# femtoBeacon-BT5_r1_0_0.net
KiCad netlist of a schematic drawn in EAGLE
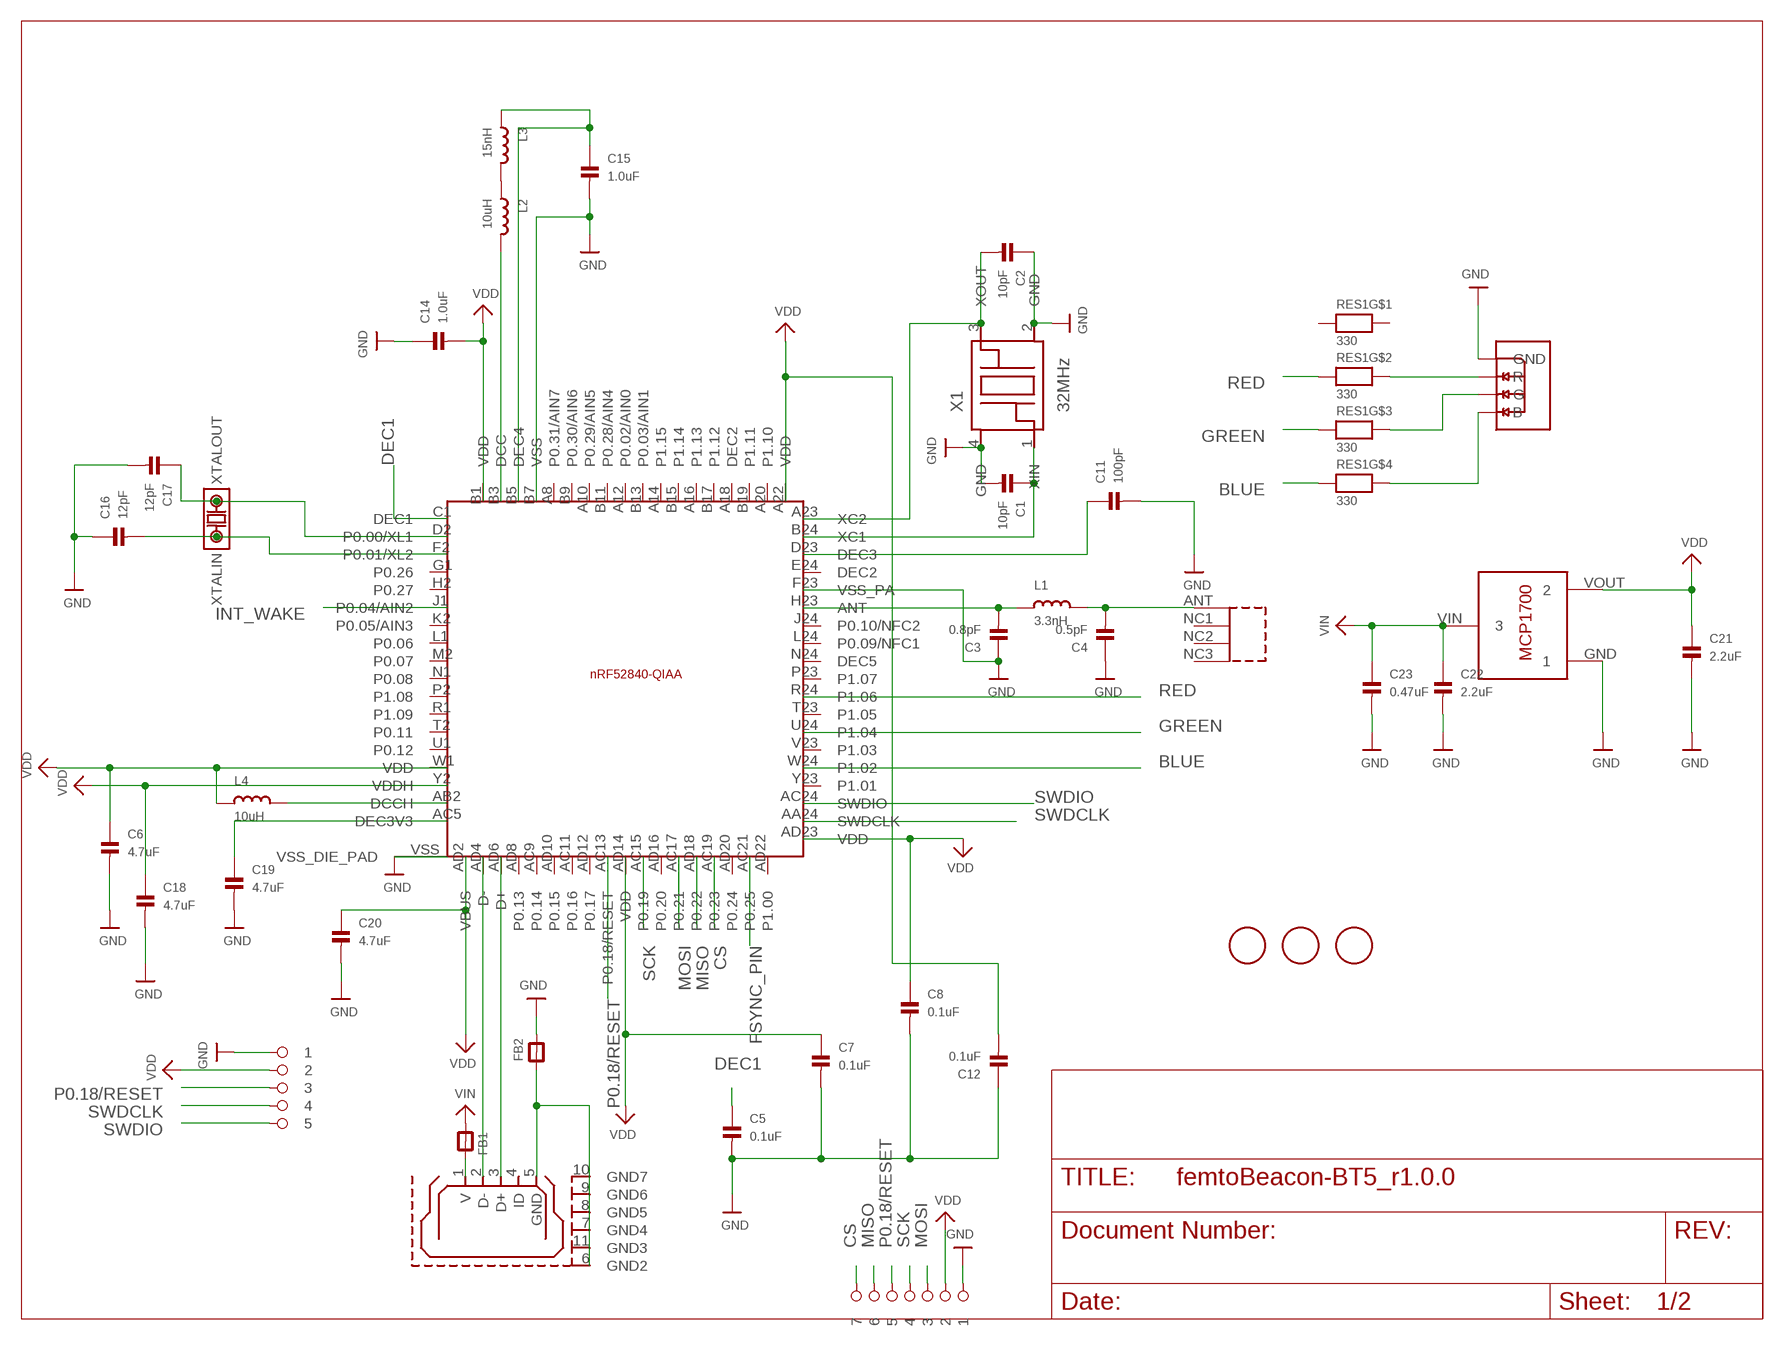
[diagram p0: schematic, sheet 1]
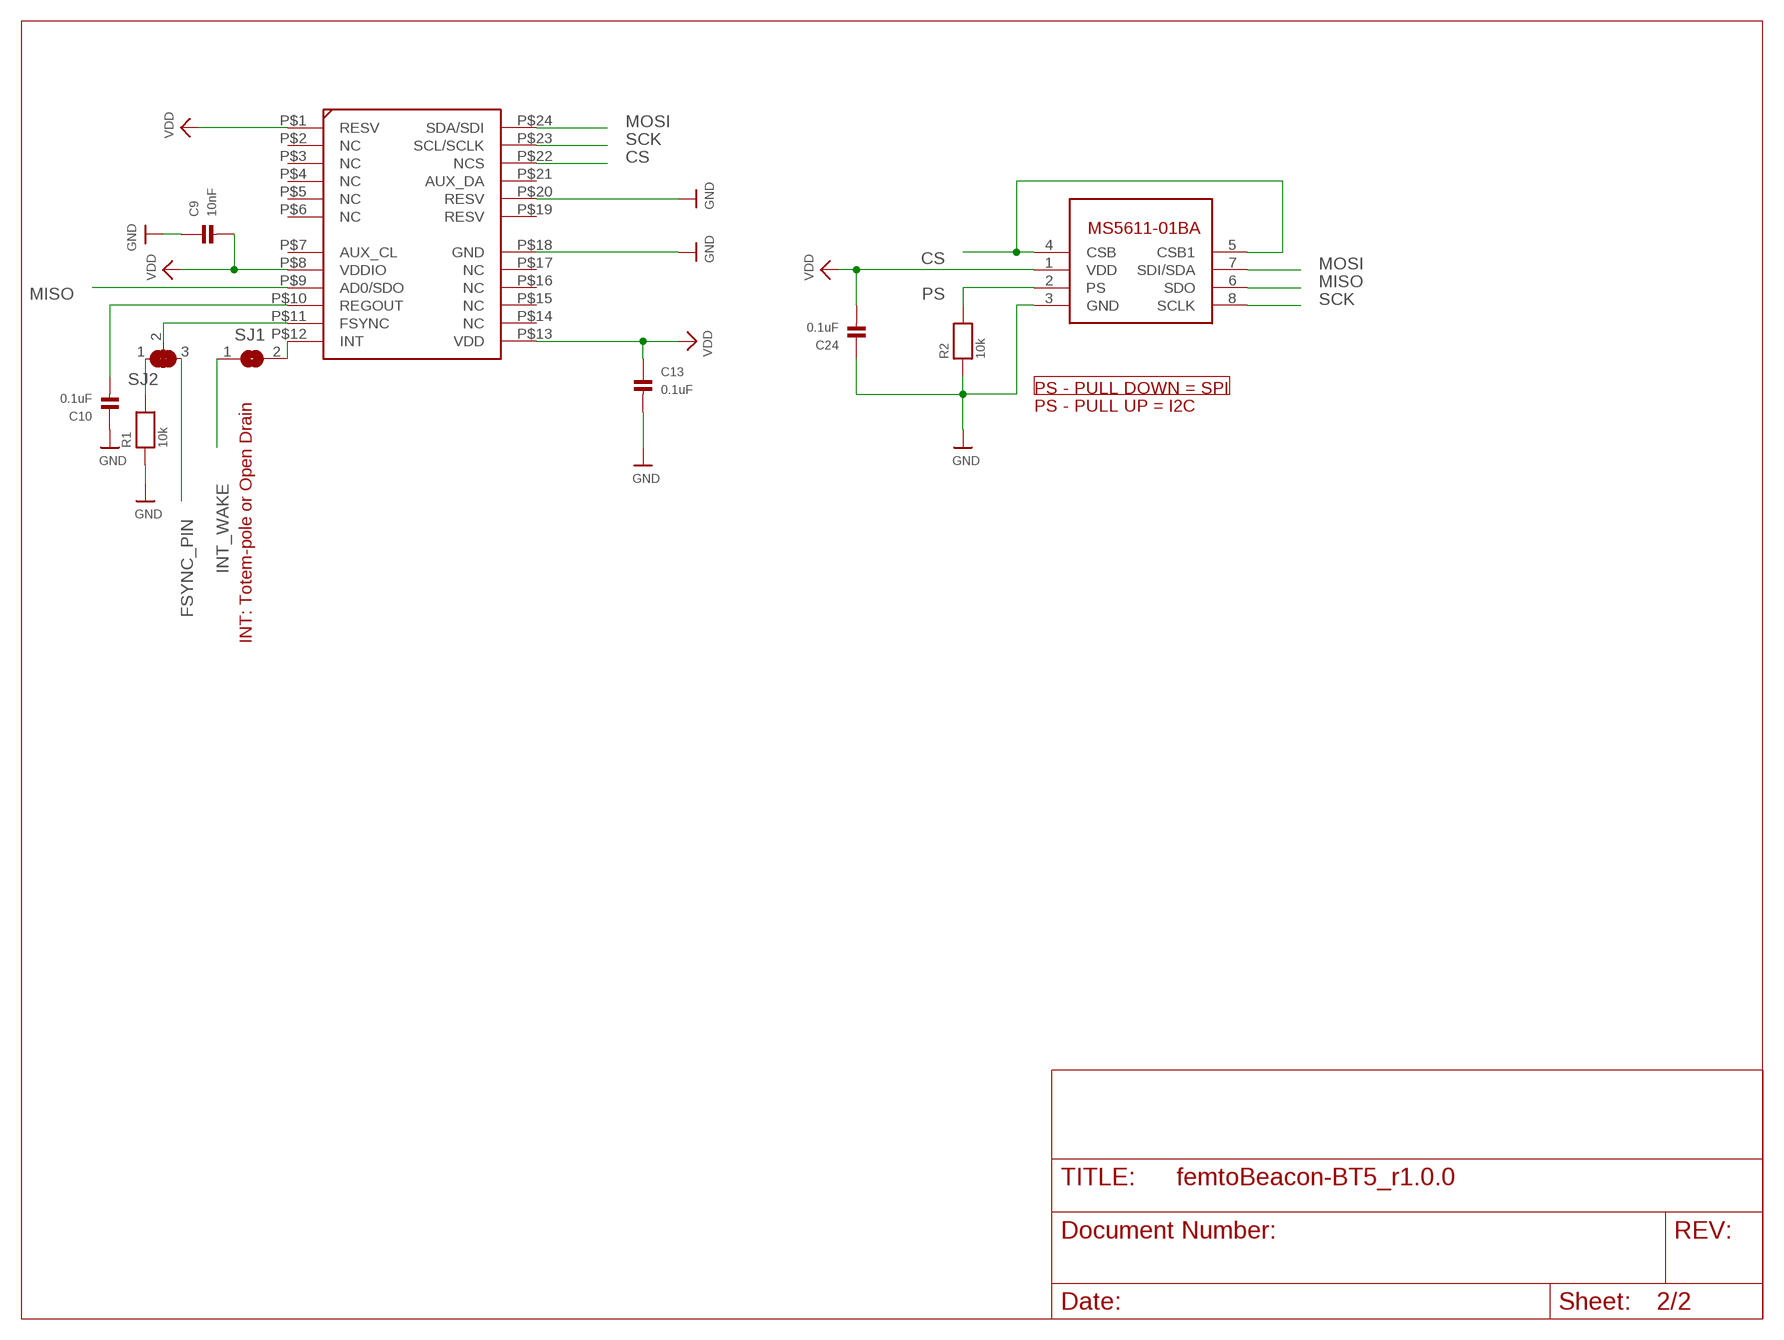
[diagram p1: schematic, sheet 2]

(export (version "E")
  (design (tool "Eeschema 10.0.6"))
  (components
    (comp (ref "BARO")
      (value "MS5611-01BA03")
      (footprint "eagle-import:MS5611-01BA03")
      (libsource (lib "eagle-import") (part "MS5611-01BA03"))
    )
    (comp (ref "C9")
      (value "10nF")
      (footprint "eagle-import:_0402MP")
      (libsource (lib "eagle-import") (part "CAP_CERAMIC_0402MP"))
    )
    (comp (ref "C10")
      (value "0.1uF")
      (footprint "eagle-import:_0402MP")
      (libsource (lib "eagle-import") (part "CAP_CERAMIC_0402MP"))
    )
    (comp (ref "C13")
      (value "0.1uF")
      (footprint "eagle-import:_0402MP")
      (libsource (lib "eagle-import") (part "CAP_CERAMIC_0402MP"))
    )
    (comp (ref "C24")
      (value "0.1uF")
      (footprint "eagle-import:_0402MP")
      (libsource (lib "eagle-import") (part "CAP_CERAMIC_0402MP"))
    )
    (comp (ref "IMU")
      (value "MPU-9250")
      (footprint "eagle-import:QFN_3X3MM")
      (libsource (lib "eagle-import") (part "MPU-9250"))
    )
    (comp (ref "R1")
      (value "10k")
      (footprint "eagle-import:_0402MP")
      (libsource (lib "eagle-import") (part "RESISTOR_0402MP"))
    )
    (comp (ref "R2")
      (value "10k")
      (footprint "eagle-import:_0402MP")
      (libsource (lib "eagle-import") (part "RESISTOR_0402MP"))
    )
    (comp (ref "SJ1")
      (value "SOLDERJUMPERCLOSED")
      (footprint "eagle-import:SOLDERJUMPER_CLOSEDWIRE")
      (libsource (lib "eagle-import") (part "SOLDERJUMPERCLOSED"))
    )
    (comp (ref "SJ2")
      (value "SOLDERJUMPER_2WAY")
      (footprint "eagle-import:SOLDERJUMPER_2WAY_OPEN_NOPASTE")
      (libsource (lib "eagle-import") (part "SOLDERJUMPER_2WAY"))
    )
    (comp (ref "ANT")
      (value "0479480001")
      (footprint "eagle-import:0479480001")
      (libsource (lib "eagle-import") (part "0479480001"))
    )
    (comp (ref "C1")
      (value "10pF")
      (footprint "eagle-import:_0402MP")
      (libsource (lib "eagle-import") (part "CAP_CERAMIC_0402MP"))
    )
    (comp (ref "C2")
      (value "10pF")
      (footprint "eagle-import:_0402MP")
      (libsource (lib "eagle-import") (part "CAP_CERAMIC_0402MP"))
    )
    (comp (ref "C3")
      (value "0.8pF")
      (footprint "eagle-import:_0402MP")
      (libsource (lib "eagle-import") (part "CAP_CERAMIC_0402MP"))
    )
    (comp (ref "C4")
      (value "0.5pF")
      (footprint "eagle-import:_0402MP")
      (libsource (lib "eagle-import") (part "CAP_CERAMIC_0402MP"))
    )
    (comp (ref "C5")
      (value "0.1uF")
      (footprint "eagle-import:_0402MP")
      (libsource (lib "eagle-import") (part "CAP_CERAMIC_0402MP"))
    )
    (comp (ref "C6")
      (value "4.7uF")
      (footprint "eagle-import:_0402MP")
      (libsource (lib "eagle-import") (part "CAP_CERAMIC_0402MP"))
    )
    (comp (ref "C7")
      (value "0.1uF")
      (footprint "eagle-import:_0402MP")
      (libsource (lib "eagle-import") (part "CAP_CERAMIC_0402MP"))
    )
    (comp (ref "C8")
      (value "0.1uF")
      (footprint "eagle-import:_0402MP")
      (libsource (lib "eagle-import") (part "CAP_CERAMIC_0402MP"))
    )
    (comp (ref "C11")
      (value "100pF")
      (footprint "eagle-import:_0402MP")
      (libsource (lib "eagle-import") (part "CAP_CERAMIC_0402MP"))
    )
    (comp (ref "C12")
      (value "0.1uF")
      (footprint "eagle-import:_0402MP")
      (libsource (lib "eagle-import") (part "CAP_CERAMIC_0402MP"))
    )
    (comp (ref "C14")
      (value "1.0uF")
      (footprint "eagle-import:_0402MP")
      (libsource (lib "eagle-import") (part "CAP_CERAMIC_0402MP"))
    )
    (comp (ref "C15")
      (value "1.0uF")
      (footprint "eagle-import:_0402MP")
      (libsource (lib "eagle-import") (part "CAP_CERAMIC_0402MP"))
    )
    (comp (ref "C16")
      (value "12pF")
      (footprint "eagle-import:_0402MP")
      (libsource (lib "eagle-import") (part "CAP_CERAMIC_0402MP"))
    )
    (comp (ref "C17")
      (value "12pF")
      (footprint "eagle-import:_0402MP")
      (libsource (lib "eagle-import") (part "CAP_CERAMIC_0402MP"))
    )
    (comp (ref "C18")
      (value "4.7uF")
      (footprint "eagle-import:_0402MP")
      (libsource (lib "eagle-import") (part "CAP_CERAMIC_0402MP"))
    )
    (comp (ref "C19")
      (value "4.7uF")
      (footprint "eagle-import:_0402MP")
      (libsource (lib "eagle-import") (part "CAP_CERAMIC_0402MP"))
    )
    (comp (ref "C20")
      (value "4.7uF")
      (footprint "eagle-import:_0402MP")
      (libsource (lib "eagle-import") (part "CAP_CERAMIC_0402MP"))
    )
    (comp (ref "C21")
      (value "2.2uF")
      (footprint "eagle-import:_0402MP")
      (libsource (lib "eagle-import") (part "CAP_CERAMIC_0402MP"))
    )
    (comp (ref "C22")
      (value "2.2uF")
      (footprint "eagle-import:_0402MP")
      (libsource (lib "eagle-import") (part "CAP_CERAMIC_0402MP"))
    )
    (comp (ref "C23")
      (value "0.47uF")
      (footprint "eagle-import:_0402MP")
      (libsource (lib "eagle-import") (part "CAP_CERAMIC_0402MP"))
    )
    (comp (ref "FB1")
      (value "FERRITE_0603MP")
      (footprint "eagle-import:_0603MP")
      (libsource (lib "eagle-import") (part "FERRITE_0603MP"))
    )
    (comp (ref "FB2")
      (value "FERRITE_0603MP")
      (footprint "eagle-import:_0603MP")
      (libsource (lib "eagle-import") (part "FERRITE_0603MP"))
    )
    (comp (ref "FID1")
      (value "FIDUCIAL")
      (footprint "eagle-import:FIDUCIAL_1MM")
      (libsource (lib "eagle-import") (part "FIDUCIAL"))
    )
    (comp (ref "FID2")
      (value "FIDUCIAL")
      (footprint "eagle-import:FIDUCIAL_1MM")
      (libsource (lib "eagle-import") (part "FIDUCIAL"))
    )
    (comp (ref "FID3")
      (value "FIDUCIAL")
      (footprint "eagle-import:FIDUCIAL_1MM")
      (libsource (lib "eagle-import") (part "FIDUCIAL"))
    )
    (comp (ref "IC")
      (value "NRF52840")
      (footprint "eagle-import:NRF52840")
      (libsource (lib "eagle-import") (part "NRF52840"))
    )
    (comp (ref "L1")
      (value "3.3nH")
      (footprint "eagle-import:_0402MP")
      (libsource (lib "eagle-import") (part "INDUCTOR_0402MP"))
    )
    (comp (ref "L2")
      (value "10uH")
      (footprint "eagle-import:_0402MP")
      (libsource (lib "eagle-import") (part "INDUCTOR_0402MP"))
    )
    (comp (ref "L3")
      (value "15nH")
      (footprint "eagle-import:_0402MP")
      (libsource (lib "eagle-import") (part "INDUCTOR_0402MP"))
    )
    (comp (ref "L4")
      (value "10uH")
      (footprint "eagle-import:_0402MP")
      (libsource (lib "eagle-import") (part "INDUCTOR_0402MP"))
    )
    (comp (ref "LDO_VREG")
      (value "MCP1700T-3302E/TT")
      (footprint "eagle-import:MCP1700T-3302E_TT")
      (libsource (lib "eagle-import") (part "MCP1700T-3302E/TT"))
    )
    (comp (ref "RES1")
      (value "330")
      (footprint "eagle-import:RESPACK_4X0603")
      (fields (field (name "MFN_ID") "741C083331JP"))
      (libsource (lib "eagle-import") (part "RESISTOR_4PACK"))
    )
    (comp (ref "U$1")
      (value "1X5_ROUND")
      (footprint "eagle-import:1X5_ROUND")
      (libsource (lib "eagle-import") (part "1X5_ROUND"))
    )
    (comp (ref "U$7")
      (value "LRTB_R48G")
      (footprint "eagle-import:LRTB_R48G")
      (libsource (lib "eagle-import") (part "LRTB_R48G"))
    )
    (comp (ref "U$27")
      (value "1X7_ROUND")
      (footprint "eagle-import:1X7_ROUND")
      (libsource (lib "eagle-import") (part "1X7_ROUND"))
    )
    (comp (ref "USB")
      (value "USB_MICROB")
      (footprint "eagle-import:USB_MICROB_PACKAGE")
      (libsource (lib "eagle-import") (part "USB_MICROB"))
    )
    (comp (ref "X1")
      (value "32MHz")
      (footprint "eagle-import:FA-128")
      (libsource (lib "eagle-import") (part "FA-128"))
    )
    (comp (ref "X2")
      (value "32.768kHZ")
      (footprint "eagle-import:ABS06-107-32.768KHZ-T")
      (libsource (lib "eagle-import") (part "ABS06-107-32.768KHZ-T"))
    )
  )
  (nets
    (net (code "1") (name "BLUE") (class "Default")
      (node (ref "IC") (pin "W24") (pinfunction "P1.02_W24") (pintype "bidirectional"))
      (node (ref "RES1") (pin "4") (pinfunction "1_4") (pintype "passive"))
    )
    (net (code "2") (name "CS") (class "Default")
      (node (ref "BARO") (pin "4") (pinfunction "CSB_4") (pintype "bidirectional"))
      (node (ref "BARO") (pin "5") (pinfunction "CSB1_5") (pintype "bidirectional"))
      (node (ref "IC") (pin "AC19") (pinfunction "P0.23_AC19") (pintype "bidirectional"))
      (node (ref "IMU") (pin "P$22") (pinfunction "NCS_P$22") (pintype "bidirectional"))
      (node (ref "U$27") (pin "P$7") (pinfunction "7_P$7") (pintype "bidirectional"))
    )
    (net (code "3") (name "DEC1") (class "Default")
      (node (ref "C5") (pin "1") (pinfunction "P$1_1") (pintype "passive"))
      (node (ref "IC") (pin "C1") (pinfunction "DEC1_C1") (pintype "bidirectional"))
    )
    (net (code "4") (name "FSYNC_PIN") (class "Default")
      (node (ref "IC") (pin "AC21") (pinfunction "P0.25_AC21") (pintype "bidirectional"))
      (node (ref "SJ2") (pin "3") (pinfunction "3_3") (pintype "passive"))
    )
    (net (code "5") (name "GND") (class "Default")
      (node (ref "BARO") (pin "3") (pinfunction "GND_3") (pintype "bidirectional"))
      (node (ref "C1") (pin "2") (pinfunction "P$2_2") (pintype "passive"))
      (node (ref "C10") (pin "1") (pinfunction "P$1_1") (pintype "passive"))
      (node (ref "C11") (pin "2") (pinfunction "P$2_2") (pintype "passive"))
      (node (ref "C12") (pin "1") (pinfunction "P$1_1") (pintype "passive"))
      (node (ref "C13") (pin "2") (pinfunction "P$2_2") (pintype "passive"))
      (node (ref "C14") (pin "1") (pinfunction "P$1_1") (pintype "passive"))
      (node (ref "C15") (pin "2") (pinfunction "P$2_2") (pintype "passive"))
      (node (ref "C16") (pin "1") (pinfunction "P$1_1") (pintype "passive"))
      (node (ref "C17") (pin "2") (pinfunction "P$2_2") (pintype "passive"))
      (node (ref "C18") (pin "2") (pinfunction "P$2_2") (pintype "passive"))
      (node (ref "C19") (pin "2") (pinfunction "P$2_2") (pintype "passive"))
      (node (ref "C2") (pin "1") (pinfunction "P$1_1") (pintype "passive"))
      (node (ref "C20") (pin "2") (pinfunction "P$2_2") (pintype "passive"))
      (node (ref "C21") (pin "2") (pinfunction "P$2_2") (pintype "passive"))
      (node (ref "C22") (pin "2") (pinfunction "P$2_2") (pintype "passive"))
      (node (ref "C23") (pin "2") (pinfunction "P$2_2") (pintype "passive"))
      (node (ref "C24") (pin "1") (pinfunction "P$1_1") (pintype "passive"))
      (node (ref "C3") (pin "1") (pinfunction "P$1_1") (pintype "passive"))
      (node (ref "C4") (pin "1") (pinfunction "P$1_1") (pintype "passive"))
      (node (ref "C5") (pin "2") (pinfunction "P$2_2") (pintype "passive"))
      (node (ref "C6") (pin "2") (pinfunction "P$2_2") (pintype "passive"))
      (node (ref "C7") (pin "2") (pinfunction "P$2_2") (pintype "passive"))
      (node (ref "C8") (pin "2") (pinfunction "P$2_2") (pintype "passive"))
      (node (ref "C9") (pin "1") (pinfunction "P$1_1") (pintype "passive"))
      (node (ref "FB2") (pin "2") (pinfunction "P$2_2") (pintype "passive"))
      (node (ref "IC") (pin "B7") (pinfunction "VSS_B7") (pintype "bidirectional"))
      (node (ref "IC") (pin "F23") (pinfunction "VSS_PA_F23") (pintype "bidirectional"))
      (node (ref "IC") (pin "VSS") (pinfunction "VSS_DIE_PAD_VSS") (pintype "bidirectional"))
      (node (ref "IMU") (pin "P$18") (pinfunction "GND_P$18") (pintype "bidirectional"))
      (node (ref "IMU") (pin "P$20") (pinfunction "RESV_P$20") (pintype "bidirectional"))
      (node (ref "LDO_VREG") (pin "GND") (pinfunction "1_GND") (pintype "bidirectional"))
      (node (ref "R1") (pin "1") (pinfunction "1_1") (pintype "passive"))
      (node (ref "R2") (pin "1") (pinfunction "1_1") (pintype "passive"))
      (node (ref "U$1") (pin "P$1") (pinfunction "1_P$1") (pintype "bidirectional"))
      (node (ref "U$27") (pin "P$1") (pinfunction "1_P$1") (pintype "bidirectional"))
      (node (ref "U$7") (pin "1") (pinfunction "GND_1") (pintype "bidirectional"))
      (node (ref "X1") (pin "2") (pinfunction "GND_2") (pintype "bidirectional"))
      (node (ref "X1") (pin "4") (pinfunction "GND_4") (pintype "bidirectional"))
    )
    (net (code "6") (name "GREEN") (class "Default")
      (node (ref "IC") (pin "U24") (pinfunction "P1.04_U24") (pintype "bidirectional"))
      (node (ref "RES1") (pin "3") (pinfunction "1_3") (pintype "passive"))
    )
    (net (code "7") (name "INT_WAKE") (class "Default")
      (node (ref "IC") (pin "J1") (pinfunction "P0.04/AIN2_J1") (pintype "bidirectional"))
      (node (ref "SJ1") (pin "1") (pinfunction "1_1") (pintype "passive"))
    )
    (net (code "8") (name "MISO") (class "Default")
      (node (ref "BARO") (pin "6") (pinfunction "SDO_6") (pintype "bidirectional"))
      (node (ref "IC") (pin "AD18") (pinfunction "P0.22_AD18") (pintype "bidirectional"))
      (node (ref "IMU") (pin "P$9") (pinfunction "AD0/SDO_P$9") (pintype "bidirectional"))
      (node (ref "U$27") (pin "P$6") (pinfunction "6_P$6") (pintype "bidirectional"))
    )
    (net (code "9") (name "MOSI") (class "Default")
      (node (ref "BARO") (pin "7") (pinfunction "SDI/SDA_7") (pintype "bidirectional"))
      (node (ref "IC") (pin "AC17") (pinfunction "P0.21_AC17") (pintype "bidirectional"))
      (node (ref "IMU") (pin "P$24") (pinfunction "SDA/SDI_P$24") (pintype "bidirectional"))
      (node (ref "U$27") (pin "P$3") (pinfunction "3_P$3") (pintype "bidirectional"))
    )
    (net (code "10") (name "Net-(ANT-1)") (class "Default")
      (node (ref "ANT") (pin "ANT") (pinfunction "1_ANT") (pintype "bidirectional"))
      (node (ref "C4") (pin "2") (pinfunction "P$2_2") (pintype "passive"))
      (node (ref "L1") (pin "2") (pinfunction "2_2") (pintype "passive"))
    )
    (net (code "11") (name "Net-(C1-P$1)") (class "Default")
      (node (ref "C1") (pin "1") (pinfunction "P$1_1") (pintype "passive"))
      (node (ref "IC") (pin "B24") (pinfunction "XC1_B24") (pintype "bidirectional"))
      (node (ref "X1") (pin "1") (pinfunction "XIN_1") (pintype "bidirectional"))
    )
    (net (code "12") (name "Net-(C2-P$2)") (class "Default")
      (node (ref "C2") (pin "2") (pinfunction "P$2_2") (pintype "passive"))
      (node (ref "IC") (pin "A23") (pinfunction "XC2_A23") (pintype "bidirectional"))
      (node (ref "X1") (pin "3") (pinfunction "XOUT_3") (pintype "bidirectional"))
    )
    (net (code "13") (name "Net-(C3-P$2)") (class "Default")
      (node (ref "C3") (pin "2") (pinfunction "P$2_2") (pintype "passive"))
      (node (ref "IC") (pin "H23") (pinfunction "ANT_H23") (pintype "bidirectional"))
      (node (ref "L1") (pin "1") (pinfunction "1_1") (pintype "passive"))
    )
    (net (code "14") (name "Net-(C10-P$2)") (class "Default")
      (node (ref "C10") (pin "2") (pinfunction "P$2_2") (pintype "passive"))
      (node (ref "IMU") (pin "P$10") (pinfunction "REGOUT_P$10") (pintype "bidirectional"))
    )
    (net (code "15") (name "Net-(C11-P$1)") (class "Default")
      (node (ref "C11") (pin "1") (pinfunction "P$1_1") (pintype "passive"))
      (node (ref "IC") (pin "D23") (pinfunction "DEC3_D23") (pintype "bidirectional"))
    )
    (net (code "16") (name "Net-(C15-P$1)") (class "Default")
      (node (ref "C15") (pin "1") (pinfunction "P$1_1") (pintype "passive"))
      (node (ref "IC") (pin "B5") (pinfunction "DEC4_B5") (pintype "bidirectional"))
      (node (ref "L3") (pin "1") (pinfunction "1_1") (pintype "passive"))
    )
    (net (code "17") (name "Net-(C16-P$2)") (class "Default")
      (node (ref "C16") (pin "2") (pinfunction "P$2_2") (pintype "passive"))
      (node (ref "IC") (pin "F2") (pinfunction "P0.01/XL2_F2") (pintype "bidirectional"))
      (node (ref "X2") (pin "1") (pinfunction "XTALIN_1") (pintype "bidirectional"))
    )
    (net (code "18") (name "Net-(C17-P$1)") (class "Default")
      (node (ref "C17") (pin "1") (pinfunction "P$1_1") (pintype "passive"))
      (node (ref "IC") (pin "D2") (pinfunction "P0.00/XL1_D2") (pintype "bidirectional"))
      (node (ref "X2") (pin "2") (pinfunction "XTALOUT_2") (pintype "bidirectional"))
    )
    (net (code "19") (name "Net-(C19-P$1)") (class "Default")
      (node (ref "C19") (pin "1") (pinfunction "P$1_1") (pintype "passive"))
      (node (ref "IC") (pin "AC5") (pinfunction "DEC3V3_AC5") (pintype "bidirectional"))
    )
    (net (code "20") (name "Net-(FB1-P$2)") (class "Default")
      (node (ref "FB1") (pin "2") (pinfunction "P$2_2") (pintype "passive"))
      (node (ref "USB") (pin "1") (pinfunction "V_1") (pintype "bidirectional"))
    )
    (net (code "21") (name "Net-(FB2-P$1)") (class "Default")
      (node (ref "FB2") (pin "1") (pinfunction "P$1_1") (pintype "passive"))
      (node (ref "USB") (pin "10") (pinfunction "GND7_10") (pintype "bidirectional"))
      (node (ref "USB") (pin "11") (pinfunction "GND3_11") (pintype "bidirectional"))
      (node (ref "USB") (pin "5") (pinfunction "GND_5") (pintype "bidirectional"))
      (node (ref "USB") (pin "6") (pinfunction "GND2_6") (pintype "bidirectional"))
      (node (ref "USB") (pin "7") (pinfunction "GND4_7") (pintype "bidirectional"))
      (node (ref "USB") (pin "8") (pinfunction "GND5_8") (pintype "bidirectional"))
      (node (ref "USB") (pin "9") (pinfunction "GND6_9") (pintype "bidirectional"))
    )
    (net (code "22") (name "Net-(IC-D+)") (class "Default")
      (node (ref "IC") (pin "AD6") (pinfunction "D+_AD6") (pintype "bidirectional"))
      (node (ref "USB") (pin "3") (pinfunction "D+_3") (pintype "bidirectional"))
    )
    (net (code "23") (name "Net-(IC-D-)") (class "Default")
      (node (ref "IC") (pin "AD4") (pinfunction "D-_AD4") (pintype "bidirectional"))
      (node (ref "USB") (pin "2") (pinfunction "D-_2") (pintype "bidirectional"))
    )
    (net (code "24") (name "Net-(IC-DCC)") (class "Default")
      (node (ref "IC") (pin "B3") (pinfunction "DCC_B3") (pintype "bidirectional"))
      (node (ref "L2") (pin "2") (pinfunction "2_2") (pintype "passive"))
    )
    (net (code "25") (name "Net-(IC-DCCH)") (class "Default")
      (node (ref "IC") (pin "AB2") (pinfunction "DCCH_AB2") (pintype "bidirectional"))
      (node (ref "L4") (pin "2") (pinfunction "2_2") (pintype "passive"))
    )
    (net (code "26") (name "Net-(IMU-FSYNC)") (class "Default")
      (node (ref "IMU") (pin "P$11") (pinfunction "FSYNC_P$11") (pintype "bidirectional"))
      (node (ref "SJ2") (pin "2") (pinfunction "2_2") (pintype "passive"))
    )
    (net (code "27") (name "Net-(IMU-INT)") (class "Default")
      (node (ref "IMU") (pin "P$12") (pinfunction "INT_P$12") (pintype "bidirectional"))
      (node (ref "SJ1") (pin "2") (pinfunction "2_2") (pintype "passive"))
    )
    (net (code "28") (name "Net-(L2-Pad1)") (class "Default")
      (node (ref "L2") (pin "1") (pinfunction "1_1") (pintype "passive"))
      (node (ref "L3") (pin "2") (pinfunction "2_2") (pintype "passive"))
    )
    (net (code "29") (name "Net-(R1-Pad2)") (class "Default")
      (node (ref "R1") (pin "2") (pinfunction "2_2") (pintype "passive"))
      (node (ref "SJ2") (pin "1") (pinfunction "1_1") (pintype "passive"))
    )
    (net (code "30") (name "Net-(RES1B-2)") (class "Default")
      (node (ref "RES1") (pin "7") (pinfunction "2_7") (pintype "passive"))
      (node (ref "U$7") (pin "2") (pinfunction "R_2") (pintype "bidirectional"))
    )
    (net (code "31") (name "Net-(RES1C-2)") (class "Default")
      (node (ref "RES1") (pin "6") (pinfunction "2_6") (pintype "passive"))
      (node (ref "U$7") (pin "3") (pinfunction "G_3") (pintype "bidirectional"))
    )
    (net (code "32") (name "Net-(RES1D-2)") (class "Default")
      (node (ref "RES1") (pin "5") (pinfunction "2_5") (pintype "passive"))
      (node (ref "U$7") (pin "4") (pinfunction "B_4") (pintype "bidirectional"))
    )
    (net (code "33") (name "P0.18{slash}RESET") (class "Default")
      (node (ref "IC") (pin "AC13") (pinfunction "P0.18/RESET_AC13") (pintype "bidirectional"))
      (node (ref "U$1") (pin "P$3") (pinfunction "3_P$3") (pintype "bidirectional"))
      (node (ref "U$27") (pin "P$5") (pinfunction "5_P$5") (pintype "bidirectional"))
    )
    (net (code "34") (name "PS") (class "Default")
      (node (ref "BARO") (pin "2") (pinfunction "PS_2") (pintype "bidirectional"))
      (node (ref "R2") (pin "2") (pinfunction "2_2") (pintype "passive"))
    )
    (net (code "35") (name "RED") (class "Default")
      (node (ref "IC") (pin "R24") (pinfunction "P1.06_R24") (pintype "bidirectional"))
      (node (ref "RES1") (pin "2") (pinfunction "1_2") (pintype "passive"))
    )
    (net (code "36") (name "SCK") (class "Default")
      (node (ref "BARO") (pin "8") (pinfunction "SCLK_8") (pintype "bidirectional"))
      (node (ref "IC") (pin "AC15") (pinfunction "P0.19_AC15") (pintype "bidirectional"))
      (node (ref "IMU") (pin "P$23") (pinfunction "SCL/SCLK_P$23") (pintype "bidirectional"))
      (node (ref "U$27") (pin "P$4") (pinfunction "4_P$4") (pintype "bidirectional"))
    )
    (net (code "37") (name "SWDCLK") (class "Default")
      (node (ref "IC") (pin "AA24") (pinfunction "SWDCLK_AA24") (pintype "bidirectional"))
      (node (ref "U$1") (pin "P$4") (pinfunction "4_P$4") (pintype "bidirectional"))
    )
    (net (code "38") (name "SWDIO") (class "Default")
      (node (ref "IC") (pin "AC24") (pinfunction "SWDIO_AC24") (pintype "bidirectional"))
      (node (ref "U$1") (pin "P$5") (pinfunction "5_P$5") (pintype "bidirectional"))
    )
    (net (code "39") (name "VDD") (class "Default")
      (node (ref "BARO") (pin "1") (pinfunction "VDD_1") (pintype "bidirectional"))
      (node (ref "C12") (pin "2") (pinfunction "P$2_2") (pintype "passive"))
      (node (ref "C13") (pin "1") (pinfunction "P$1_1") (pintype "passive"))
      (node (ref "C14") (pin "2") (pinfunction "P$2_2") (pintype "passive"))
      (node (ref "C18") (pin "1") (pinfunction "P$1_1") (pintype "passive"))
      (node (ref "C20") (pin "1") (pinfunction "P$1_1") (pintype "passive"))
      (node (ref "C21") (pin "1") (pinfunction "P$1_1") (pintype "passive"))
      (node (ref "C24") (pin "2") (pinfunction "P$2_2") (pintype "passive"))
      (node (ref "C6") (pin "1") (pinfunction "P$1_1") (pintype "passive"))
      (node (ref "C7") (pin "1") (pinfunction "P$1_1") (pintype "passive"))
      (node (ref "C8") (pin "1") (pinfunction "P$1_1") (pintype "passive"))
      (node (ref "C9") (pin "2") (pinfunction "P$2_2") (pintype "passive"))
      (node (ref "IC") (pin "A22") (pinfunction "VDD_A22") (pintype "bidirectional"))
      (node (ref "IC") (pin "AD14") (pinfunction "VDD_AD14") (pintype "bidirectional"))
      (node (ref "IC") (pin "AD2") (pinfunction "VBUS_AD2") (pintype "bidirectional"))
      (node (ref "IC") (pin "AD23") (pinfunction "VDD_AD23") (pintype "bidirectional"))
      (node (ref "IC") (pin "B1") (pinfunction "VDD_B1") (pintype "bidirectional"))
      (node (ref "IC") (pin "W1") (pinfunction "VDD_W1") (pintype "bidirectional"))
      (node (ref "IC") (pin "Y2") (pinfunction "VDDH_Y2") (pintype "bidirectional"))
      (node (ref "IMU") (pin "P$1") (pinfunction "RESV_P$1") (pintype "bidirectional"))
      (node (ref "IMU") (pin "P$13") (pinfunction "VDD_P$13") (pintype "bidirectional"))
      (node (ref "IMU") (pin "P$8") (pinfunction "VDDIO_P$8") (pintype "bidirectional"))
      (node (ref "L4") (pin "1") (pinfunction "1_1") (pintype "passive"))
      (node (ref "LDO_VREG") (pin "VOUT") (pinfunction "2_VOUT") (pintype "bidirectional"))
      (node (ref "U$1") (pin "P$2") (pinfunction "2_P$2") (pintype "bidirectional"))
      (node (ref "U$27") (pin "P$2") (pinfunction "2_P$2") (pintype "bidirectional"))
    )
    (net (code "40") (name "VIN") (class "Default")
      (node (ref "C22") (pin "1") (pinfunction "P$1_1") (pintype "passive"))
      (node (ref "C23") (pin "1") (pinfunction "P$1_1") (pintype "passive"))
      (node (ref "FB1") (pin "1") (pinfunction "P$1_1") (pintype "passive"))
      (node (ref "LDO_VREG") (pin "VIN") (pinfunction "3_VIN") (pintype "bidirectional"))
    )
    (net (code "41") (name "unconnected-(ANT-2-PadNC1)") (class "Default")
      (node (ref "ANT") (pin "NC1") (pinfunction "2_NC1") (pintype "bidirectional"))
    )
    (net (code "42") (name "unconnected-(ANT-3-PadNC2)") (class "Default")
      (node (ref "ANT") (pin "NC2") (pinfunction "3_NC2") (pintype "bidirectional"))
    )
    (net (code "43") (name "unconnected-(ANT-4-PadNC3)") (class "Default")
      (node (ref "ANT") (pin "NC3") (pinfunction "4_NC3") (pintype "bidirectional"))
    )
    (net (code "44") (name "unconnected-(IC-DEC2-PadA18)") (class "Default")
      (node (ref "IC") (pin "A18") (pinfunction "DEC2_A18") (pintype "bidirectional"))
    )
    (net (code "45") (name "unconnected-(IC-DEC2-PadE24)") (class "Default")
      (node (ref "IC") (pin "E24") (pinfunction "DEC2_E24") (pintype "bidirectional"))
    )
    (net (code "46") (name "unconnected-(IC-DEC5-PadN24)") (class "Default")
      (node (ref "IC") (pin "N24") (pinfunction "DEC5_N24") (pintype "bidirectional"))
    )
    (net (code "47") (name "unconnected-(IC-P0.02{slash}AIN0-PadA12)") (class "Default")
      (node (ref "IC") (pin "A12") (pinfunction "P0.02/AIN0_A12") (pintype "bidirectional"))
    )
    (net (code "48") (name "unconnected-(IC-P0.03{slash}AIN1-PadB13)") (class "Default")
      (node (ref "IC") (pin "B13") (pinfunction "P0.03/AIN1_B13") (pintype "bidirectional"))
    )
    (net (code "49") (name "unconnected-(IC-P0.05{slash}AIN3-PadK2)") (class "Default")
      (node (ref "IC") (pin "K2") (pinfunction "P0.05/AIN3_K2") (pintype "bidirectional"))
    )
    (net (code "50") (name "unconnected-(IC-P0.06-PadL1)") (class "Default")
      (node (ref "IC") (pin "L1") (pinfunction "P0.06_L1") (pintype "bidirectional"))
    )
    (net (code "51") (name "unconnected-(IC-P0.07-PadM2)") (class "Default")
      (node (ref "IC") (pin "M2") (pinfunction "P0.07_M2") (pintype "bidirectional"))
    )
    (net (code "52") (name "unconnected-(IC-P0.08-PadN1)") (class "Default")
      (node (ref "IC") (pin "N1") (pinfunction "P0.08_N1") (pintype "bidirectional"))
    )
    (net (code "53") (name "unconnected-(IC-P0.09{slash}NFC1-PadL24)") (class "Default")
      (node (ref "IC") (pin "L24") (pinfunction "P0.09/NFC1_L24") (pintype "bidirectional"))
    )
    (net (code "54") (name "unconnected-(IC-P0.10{slash}NFC2-PadJ24)") (class "Default")
      (node (ref "IC") (pin "J24") (pinfunction "P0.10/NFC2_J24") (pintype "bidirectional"))
    )
    (net (code "55") (name "unconnected-(IC-P0.11-PadT2)") (class "Default")
      (node (ref "IC") (pin "T2") (pinfunction "P0.11_T2") (pintype "bidirectional"))
    )
    (net (code "56") (name "unconnected-(IC-P0.12-PadU1)") (class "Default")
      (node (ref "IC") (pin "U1") (pinfunction "P0.12_U1") (pintype "bidirectional"))
    )
    (net (code "57") (name "unconnected-(IC-P0.13-PadAD8)") (class "Default")
      (node (ref "IC") (pin "AD8") (pinfunction "P0.13_AD8") (pintype "bidirectional"))
    )
    (net (code "58") (name "unconnected-(IC-P0.14-PadAC9)") (class "Default")
      (node (ref "IC") (pin "AC9") (pinfunction "P0.14_AC9") (pintype "bidirectional"))
    )
    (net (code "59") (name "unconnected-(IC-P0.15-PadAD10)") (class "Default")
      (node (ref "IC") (pin "AD10") (pinfunction "P0.15_AD10") (pintype "bidirectional"))
    )
    (net (code "60") (name "unconnected-(IC-P0.16-PadAC11)") (class "Default")
      (node (ref "IC") (pin "AC11") (pinfunction "P0.16_AC11") (pintype "bidirectional"))
    )
    (net (code "61") (name "unconnected-(IC-P0.17-PadAD12)") (class "Default")
      (node (ref "IC") (pin "AD12") (pinfunction "P0.17_AD12") (pintype "bidirectional"))
    )
    (net (code "62") (name "unconnected-(IC-P0.20-PadAD16)") (class "Default")
      (node (ref "IC") (pin "AD16") (pinfunction "P0.20_AD16") (pintype "bidirectional"))
    )
    (net (code "63") (name "unconnected-(IC-P0.24-PadAD20)") (class "Default")
      (node (ref "IC") (pin "AD20") (pinfunction "P0.24_AD20") (pintype "bidirectional"))
    )
    (net (code "64") (name "unconnected-(IC-P0.26-PadG1)") (class "Default")
      (node (ref "IC") (pin "G1") (pinfunction "P0.26_G1") (pintype "bidirectional"))
    )
    (net (code "65") (name "unconnected-(IC-P0.27-PadH2)") (class "Default")
      (node (ref "IC") (pin "H2") (pinfunction "P0.27_H2") (pintype "bidirectional"))
    )
    (net (code "66") (name "unconnected-(IC-P0.28{slash}AIN4-PadB11)") (class "Default")
      (node (ref "IC") (pin "B11") (pinfunction "P0.28/AIN4_B11") (pintype "bidirectional"))
    )
    (net (code "67") (name "unconnected-(IC-P0.29{slash}AIN5-PadA10)") (class "Default")
      (node (ref "IC") (pin "A10") (pinfunction "P0.29/AIN5_A10") (pintype "bidirectional"))
    )
    (net (code "68") (name "unconnected-(IC-P0.30{slash}AIN6-PadB9)") (class "Default")
      (node (ref "IC") (pin "B9") (pinfunction "P0.30/AIN6_B9") (pintype "bidirectional"))
    )
    (net (code "69") (name "unconnected-(IC-P0.31{slash}AIN7-PadA8)") (class "Default")
      (node (ref "IC") (pin "A8") (pinfunction "P0.31/AIN7_A8") (pintype "bidirectional"))
    )
    (net (code "70") (name "unconnected-(IC-P1.00-PadAD22)") (class "Default")
      (node (ref "IC") (pin "AD22") (pinfunction "P1.00_AD22") (pintype "bidirectional"))
    )
    (net (code "71") (name "unconnected-(IC-P1.01-PadY23)") (class "Default")
      (node (ref "IC") (pin "Y23") (pinfunction "P1.01_Y23") (pintype "bidirectional"))
    )
    (net (code "72") (name "unconnected-(IC-P1.03-PadV23)") (class "Default")
      (node (ref "IC") (pin "V23") (pinfunction "P1.03_V23") (pintype "bidirectional"))
    )
    (net (code "73") (name "unconnected-(IC-P1.05-PadT23)") (class "Default")
      (node (ref "IC") (pin "T23") (pinfunction "P1.05_T23") (pintype "bidirectional"))
    )
    (net (code "74") (name "unconnected-(IC-P1.07-PadP23)") (class "Default")
      (node (ref "IC") (pin "P23") (pinfunction "P1.07_P23") (pintype "bidirectional"))
    )
    (net (code "75") (name "unconnected-(IC-P1.08-PadP2)") (class "Default")
      (node (ref "IC") (pin "P2") (pinfunction "P1.08_P2") (pintype "bidirectional"))
    )
    (net (code "76") (name "unconnected-(IC-P1.09-PadR1)") (class "Default")
      (node (ref "IC") (pin "R1") (pinfunction "P1.09_R1") (pintype "bidirectional"))
    )
    (net (code "77") (name "unconnected-(IC-P1.10-PadA20)") (class "Default")
      (node (ref "IC") (pin "A20") (pinfunction "P1.10_A20") (pintype "bidirectional"))
    )
    (net (code "78") (name "unconnected-(IC-P1.11-PadB19)") (class "Default")
      (node (ref "IC") (pin "B19") (pinfunction "P1.11_B19") (pintype "bidirectional"))
    )
    (net (code "79") (name "unconnected-(IC-P1.12-PadB17)") (class "Default")
      (node (ref "IC") (pin "B17") (pinfunction "P1.12_B17") (pintype "bidirectional"))
    )
    (net (code "80") (name "unconnected-(IC-P1.13-PadA16)") (class "Default")
      (node (ref "IC") (pin "A16") (pinfunction "P1.13_A16") (pintype "bidirectional"))
    )
    (net (code "81") (name "unconnected-(IC-P1.14-PadB15)") (class "Default")
      (node (ref "IC") (pin "B15") (pinfunction "P1.14_B15") (pintype "bidirectional"))
    )
    (net (code "82") (name "unconnected-(IC-P1.15-PadA14)") (class "Default")
      (node (ref "IC") (pin "A14") (pinfunction "P1.15_A14") (pintype "bidirectional"))
    )
    (net (code "83") (name "unconnected-(IMU-AUX_CL-PadP$7)") (class "Default")
      (node (ref "IMU") (pin "P$7") (pinfunction "AUX_CL_P$7") (pintype "bidirectional"))
    )
    (net (code "84") (name "unconnected-(IMU-AUX_DA-PadP$21)") (class "Default")
      (node (ref "IMU") (pin "P$21") (pinfunction "AUX_DA_P$21") (pintype "bidirectional"))
    )
    (net (code "85") (name "unconnected-(IMU-NC-PadP$2)") (class "Default")
      (node (ref "IMU") (pin "P$2") (pinfunction "NC_P$2") (pintype "bidirectional"))
    )
    (net (code "86") (name "unconnected-(IMU-NC-PadP$3)") (class "Default")
      (node (ref "IMU") (pin "P$3") (pinfunction "NC_P$3") (pintype "bidirectional"))
    )
    (net (code "87") (name "unconnected-(IMU-NC-PadP$4)") (class "Default")
      (node (ref "IMU") (pin "P$4") (pinfunction "NC_P$4") (pintype "bidirectional"))
    )
    (net (code "88") (name "unconnected-(IMU-NC-PadP$5)") (class "Default")
      (node (ref "IMU") (pin "P$5") (pinfunction "NC_P$5") (pintype "bidirectional"))
    )
    (net (code "89") (name "unconnected-(IMU-NC-PadP$6)") (class "Default")
      (node (ref "IMU") (pin "P$6") (pinfunction "NC_P$6") (pintype "bidirectional"))
    )
    (net (code "90") (name "unconnected-(IMU-NC-PadP$14)") (class "Default")
      (node (ref "IMU") (pin "P$14") (pinfunction "NC_P$14") (pintype "bidirectional"))
    )
    (net (code "91") (name "unconnected-(IMU-NC-PadP$15)") (class "Default")
      (node (ref "IMU") (pin "P$15") (pinfunction "NC_P$15") (pintype "bidirectional"))
    )
    (net (code "92") (name "unconnected-(IMU-NC-PadP$16)") (class "Default")
      (node (ref "IMU") (pin "P$16") (pinfunction "NC_P$16") (pintype "bidirectional"))
    )
    (net (code "93") (name "unconnected-(IMU-NC-PadP$17)") (class "Default")
      (node (ref "IMU") (pin "P$17") (pinfunction "NC_P$17") (pintype "bidirectional"))
    )
    (net (code "94") (name "unconnected-(IMU-RESV-PadP$19)") (class "Default")
      (node (ref "IMU") (pin "P$19") (pinfunction "RESV_P$19") (pintype "bidirectional"))
    )
    (net (code "95") (name "unconnected-(RES1-Pad1)") (class "Default")
      (node (ref "RES1") (pin "1") (pinfunction "1_1") (pintype "passive"))
    )
    (net (code "96") (name "unconnected-(RES1A-2-Pad8)") (class "Default")
      (node (ref "RES1") (pin "8") (pinfunction "2_8") (pintype "passive"))
    )
    (net (code "97") (name "unconnected-(USB-ID-Pad4)") (class "Default")
      (node (ref "USB") (pin "4") (pinfunction "ID_4") (pintype "bidirectional"))
    )
  )
)
